# ZaehlerSDM72_RS485_mit_Serial_swap-optim.net
KiCad netlist of a schematic drawn in EAGLE
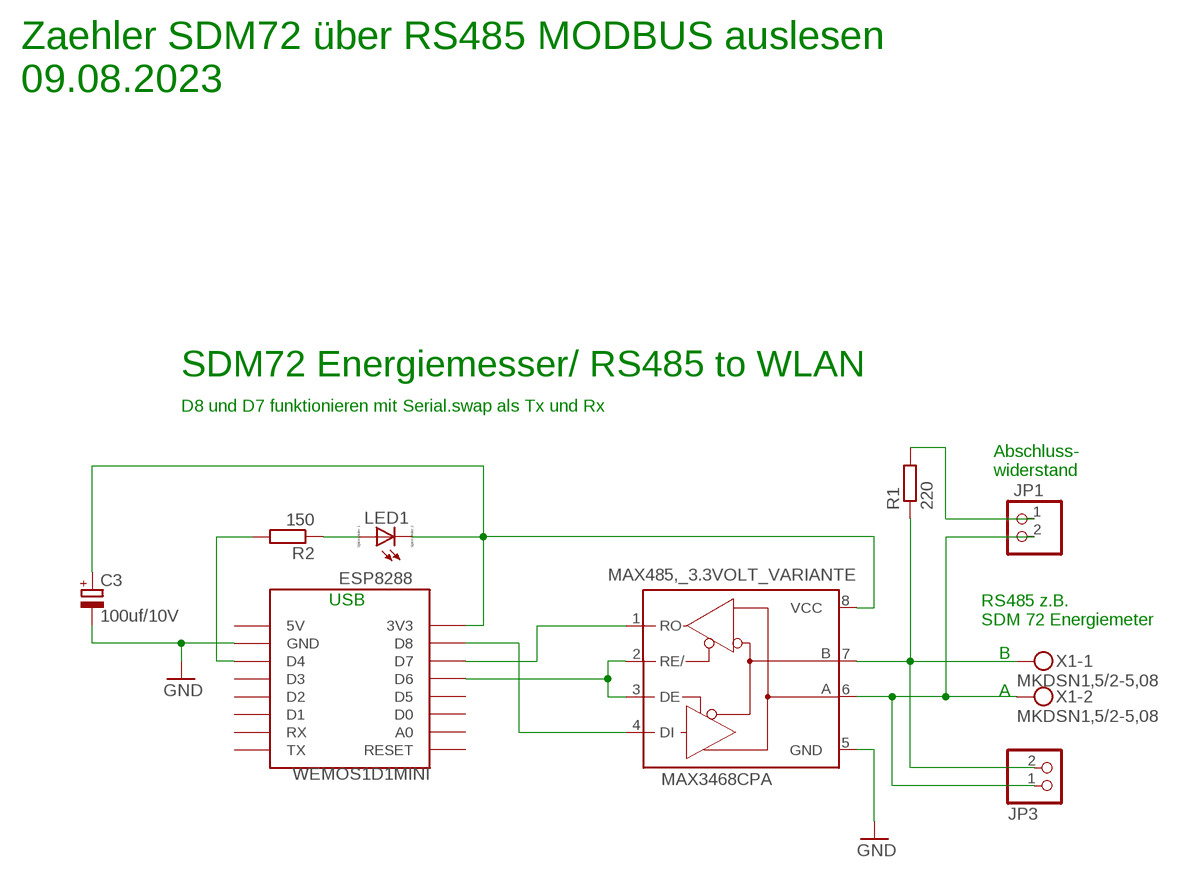
[diagram p0: schematic, sheet 1]

(export (version "E")
  (design (tool "Eeschema 10.0.6"))
  (components
    (comp (ref "C3")
      (value "100uf/10V")
      (footprint "eagle-import:E2,5-7")
      (libsource (lib "eagle-import") (part "CPOL-EUE2.5-7"))
    )
    (comp (ref "JP1")
      (value "PINHD-1X2/90")
      (footprint "eagle-import:1X02_90")
      (libsource (lib "eagle-import") (part "PINHD-1X2/90"))
    )
    (comp (ref "JP3")
      (value "PINHD-1X2/90")
      (footprint "eagle-import:1X02_90")
      (libsource (lib "eagle-import") (part "PINHD-1X2/90"))
    )
    (comp (ref "LED1")
      (value "LED_ELD260")
      (footprint "eagle-import:LED_LD260")
      (libsource (lib "eagle-import") (part "LED_ELD260"))
    )
    (comp (ref "MAX485,_3.3VOLT_VARIANTE")
      (value "MAX3468CPA")
      (footprint "eagle-import:DIL08")
      (libsource (lib "eagle-import") (part "MAX34PA68C"))
    )
    (comp (ref "R1")
      (value "220")
      (footprint "eagle-import:0207_5V")
      (libsource (lib "eagle-import") (part "R-EU_0207/5V"))
    )
    (comp (ref "R2")
      (value "150")
      (footprint "eagle-import:0207_5V")
      (libsource (lib "eagle-import") (part "R-EU_0207/5V"))
    )
    (comp (ref "WEMOS1D1MINI")
      (value "ESP8288")
      (footprint "eagle-import:WEMOS-D1-MINI")
      (libsource (lib "eagle-import") (part "WEMOS-D1-MINI"))
    )
    (comp (ref "X1")
      (value "MKDSN1,5/2-5,08")
      (footprint "eagle-import:MKDSN1,5_2-5,08")
      (libsource (lib "eagle-import") (part "MKDSN1,5/2-5,08"))
    )
  )
  (nets
    (net (code "1") (name "GND") (class "Default")
      (node (ref "C3") (pin "-") (pinfunction "-_-") (pintype "passive"))
      (node (ref "MAX485,_3.3VOLT_VARIANTE") (pin "5") (pinfunction "GND_5") (pintype "power_in"))
      (node (ref "WEMOS1D1MINI") (pin "GND") (pinfunction "GND_GND") (pintype "bidirectional"))
    )
    (net (code "2") (name "Net-(JP1-Pad1)") (class "Default")
      (node (ref "JP1") (pin "1") (pinfunction "1_1") (pintype "passive"))
      (node (ref "R1") (pin "2") (pinfunction "2_2") (pintype "passive"))
    )
    (net (code "3") (name "Net-(LED1-C)") (class "Default")
      (node (ref "C3") (pin "+") (pinfunction "+_+") (pintype "passive"))
      (node (ref "LED1") (pin "K") (pinfunction "C_K") (pintype "passive"))
      (node (ref "MAX485,_3.3VOLT_VARIANTE") (pin "8") (pinfunction "VCC_8") (pintype "power_in"))
      (node (ref "WEMOS1D1MINI") (pin "3V3") (pinfunction "3V3_3V3") (pintype "bidirectional"))
    )
    (net (code "4") (name "Net-(LED1-PadA)") (class "Default")
      (node (ref "LED1") (pin "A") (pinfunction "A_A") (pintype "passive"))
      (node (ref "R2") (pin "1") (pinfunction "1_1") (pintype "passive"))
    )
    (net (code "5") (name "Net-(MAX485,_3.3VOLT_VARIANTE-A)") (class "Default")
      (node (ref "JP1") (pin "2") (pinfunction "2_2") (pintype "passive"))
      (node (ref "JP3") (pin "1") (pinfunction "1_1") (pintype "passive"))
      (node (ref "MAX485,_3.3VOLT_VARIANTE") (pin "6") (pinfunction "A_6") (pintype "passive"))
      (node (ref "X1") (pin "2") (pinfunction "KL_2") (pintype "passive"))
    )
    (net (code "6") (name "Net-(MAX485,_3.3VOLT_VARIANTE-B)") (class "Default")
      (node (ref "JP3") (pin "2") (pinfunction "2_2") (pintype "passive"))
      (node (ref "MAX485,_3.3VOLT_VARIANTE") (pin "7") (pinfunction "B_7") (pintype "passive"))
      (node (ref "R1") (pin "1") (pinfunction "1_1") (pintype "passive"))
      (node (ref "X1") (pin "1") (pinfunction "KL_1") (pintype "passive"))
    )
    (net (code "7") (name "Net-(MAX485,_3.3VOLT_VARIANTE-DE)") (class "Default")
      (node (ref "MAX485,_3.3VOLT_VARIANTE") (pin "2") (pinfunction "RE/_2") (pintype "input"))
      (node (ref "MAX485,_3.3VOLT_VARIANTE") (pin "3") (pinfunction "DE_3") (pintype "input"))
      (node (ref "WEMOS1D1MINI") (pin "D6") (pinfunction "D6_D6") (pintype "bidirectional"))
    )
    (net (code "8") (name "Net-(MAX485,_3.3VOLT_VARIANTE-DI)") (class "Default")
      (node (ref "MAX485,_3.3VOLT_VARIANTE") (pin "4") (pinfunction "DI_4") (pintype "input"))
      (node (ref "WEMOS1D1MINI") (pin "D8") (pinfunction "D8_D8") (pintype "bidirectional"))
    )
    (net (code "9") (name "Net-(MAX485,_3.3VOLT_VARIANTE-RO)") (class "Default")
      (node (ref "MAX485,_3.3VOLT_VARIANTE") (pin "1") (pinfunction "RO_1") (pintype "output"))
      (node (ref "WEMOS1D1MINI") (pin "D7") (pinfunction "D7_D7") (pintype "bidirectional"))
    )
    (net (code "10") (name "Net-(R2-Pad2)") (class "Default")
      (node (ref "R2") (pin "2") (pinfunction "2_2") (pintype "passive"))
      (node (ref "WEMOS1D1MINI") (pin "D4") (pinfunction "D4_D4") (pintype "bidirectional"))
    )
    (net (code "11") (name "unconnected-(WEMOS1D1MINI-Pad5V)") (class "Default")
      (node (ref "WEMOS1D1MINI") (pin "5V") (pinfunction "5V_5V") (pintype "bidirectional"))
    )
    (net (code "12") (name "unconnected-(WEMOS1D1MINI-PadA0)") (class "Default")
      (node (ref "WEMOS1D1MINI") (pin "A0") (pinfunction "A0_A0") (pintype "bidirectional"))
    )
    (net (code "13") (name "unconnected-(WEMOS1D1MINI-PadD0)") (class "Default")
      (node (ref "WEMOS1D1MINI") (pin "D0") (pinfunction "D0_D0") (pintype "bidirectional"))
    )
    (net (code "14") (name "unconnected-(WEMOS1D1MINI-PadD1)") (class "Default")
      (node (ref "WEMOS1D1MINI") (pin "D1") (pinfunction "D1_D1") (pintype "bidirectional"))
    )
    (net (code "15") (name "unconnected-(WEMOS1D1MINI-PadD2)") (class "Default")
      (node (ref "WEMOS1D1MINI") (pin "D2") (pinfunction "D2_D2") (pintype "bidirectional"))
    )
    (net (code "16") (name "unconnected-(WEMOS1D1MINI-PadD3)") (class "Default")
      (node (ref "WEMOS1D1MINI") (pin "D3") (pinfunction "D3_D3") (pintype "bidirectional"))
    )
    (net (code "17") (name "unconnected-(WEMOS1D1MINI-PadD5)") (class "Default")
      (node (ref "WEMOS1D1MINI") (pin "D5") (pinfunction "D5_D5") (pintype "bidirectional"))
    )
    (net (code "18") (name "unconnected-(WEMOS1D1MINI-PadRESET)") (class "Default")
      (node (ref "WEMOS1D1MINI") (pin "RESET") (pinfunction "RESET_RESET") (pintype "bidirectional"))
    )
    (net (code "19") (name "unconnected-(WEMOS1D1MINI-PadRX)") (class "Default")
      (node (ref "WEMOS1D1MINI") (pin "RX") (pinfunction "RX_RX") (pintype "bidirectional"))
    )
    (net (code "20") (name "unconnected-(WEMOS1D1MINI-PadTX)") (class "Default")
      (node (ref "WEMOS1D1MINI") (pin "TX") (pinfunction "TX_TX") (pintype "bidirectional"))
    )
  )
)
